# Pendulum_Lamp_PCB.net
KiCad netlist of a schematic drawn in EAGLE
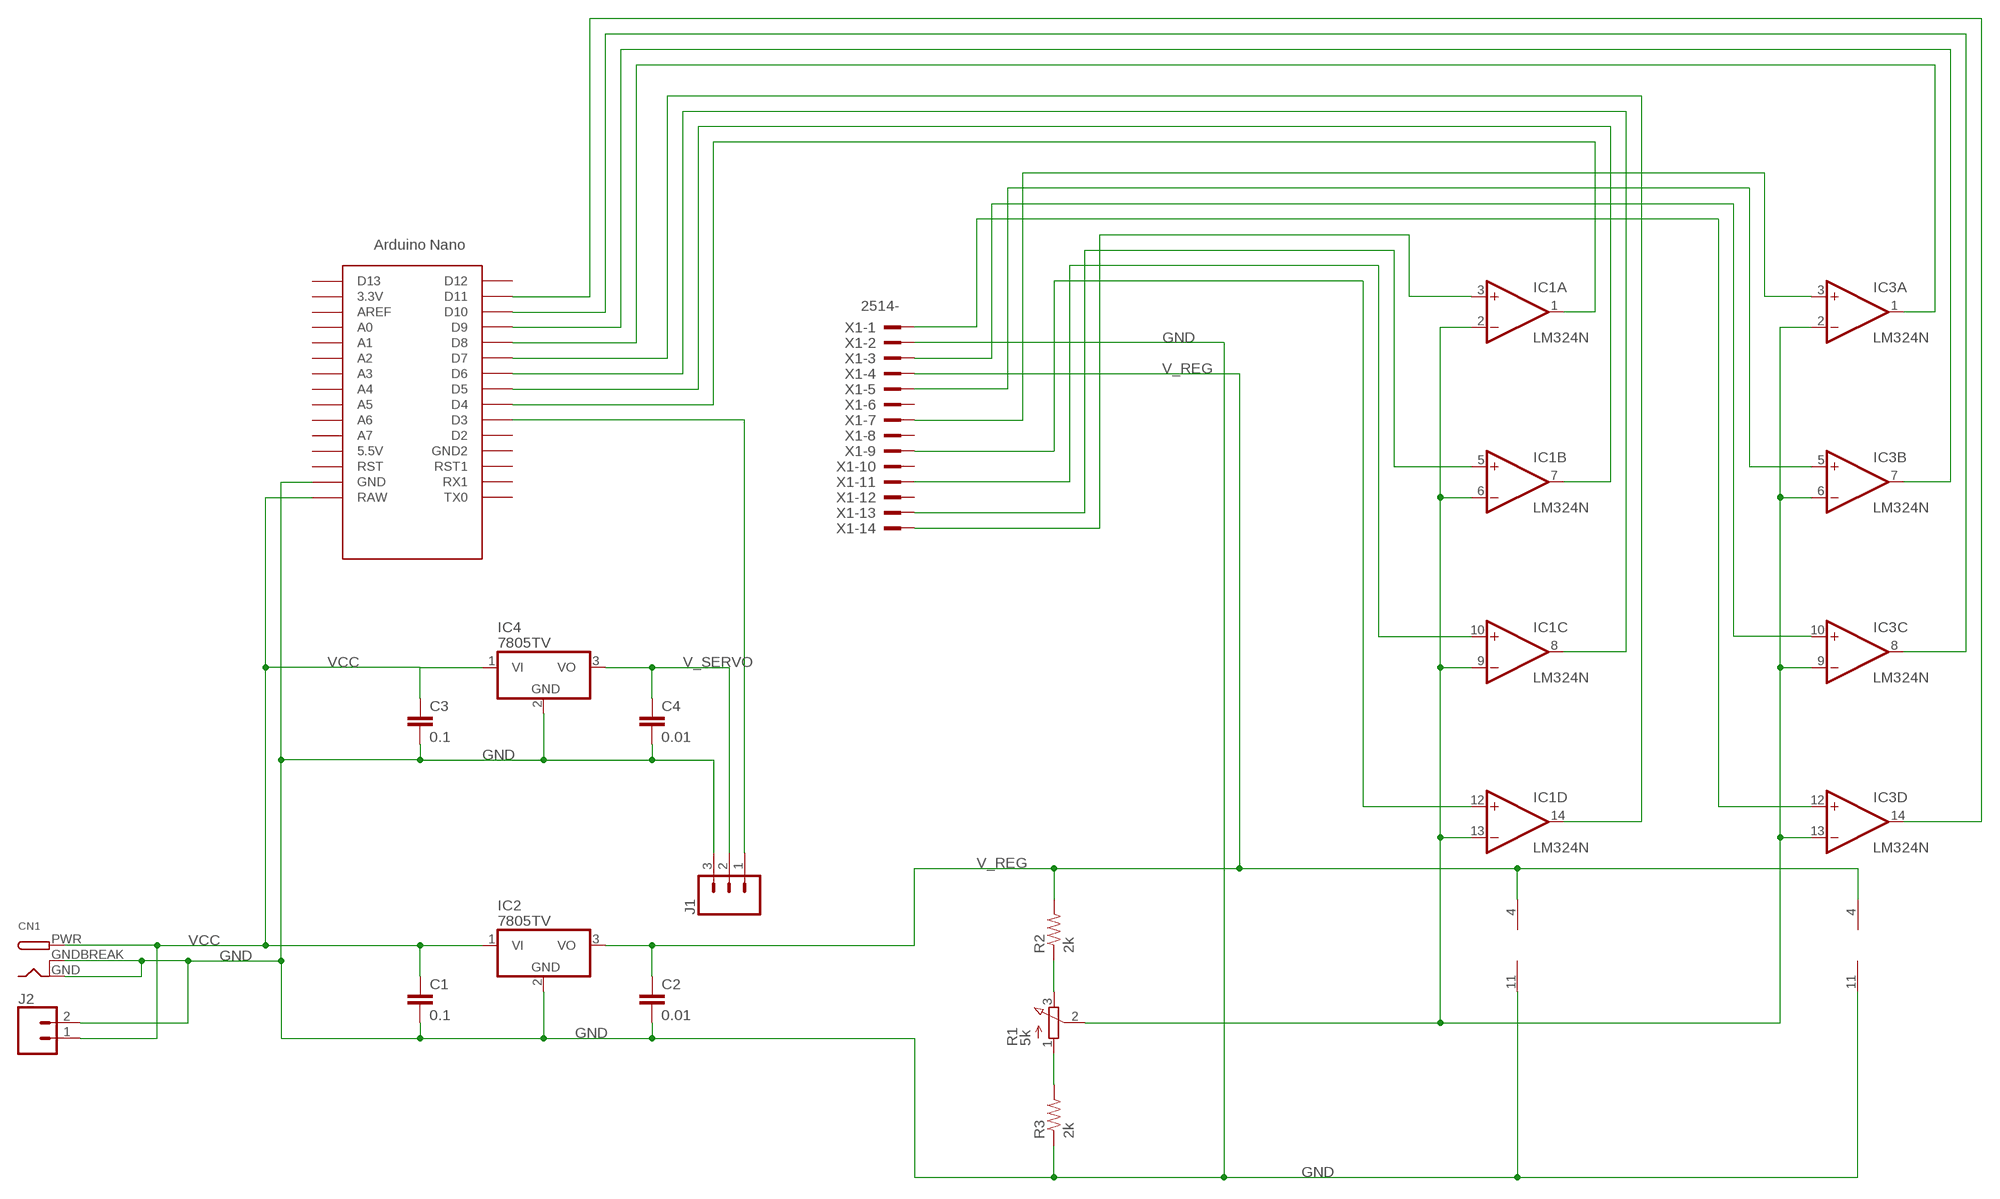
[diagram p0: schematic, sheet 1]

(export (version "E")
  (design (tool "Eeschema 10.0.6"))
  (components
    (comp (ref "C1")
      (value "0.1")
      (footprint "eagle-import:C025-030X050")
      (libsource (lib "eagle-import") (part "C-EU025-030X050"))
    )
    (comp (ref "C2")
      (value "0.01")
      (footprint "eagle-import:C025-030X050")
      (libsource (lib "eagle-import") (part "C-EU025-030X050"))
    )
    (comp (ref "C3")
      (value "0.1")
      (footprint "eagle-import:C025-030X050")
      (libsource (lib "eagle-import") (part "C-EU025-030X050"))
    )
    (comp (ref "C4")
      (value "0.01")
      (footprint "eagle-import:C025-030X050")
      (libsource (lib "eagle-import") (part "C-EU025-030X050"))
    )
    (comp (ref "CN1")
      (value "DCBARRELPTH")
      (footprint "eagle-import:DCJACK_2MM_PTH")
      (libsource (lib "eagle-import") (part "DCBARRELPTH"))
    )
    (comp (ref "IC1")
      (value "LM324N")
      (footprint "eagle-import:DIL14")
      (libsource (lib "eagle-import") (part "LM324N"))
    )
    (comp (ref "IC2")
      (value "7805TV")
      (footprint "eagle-import:TO220V")
      (libsource (lib "eagle-import") (part "78TV05"))
    )
    (comp (ref "IC3")
      (value "LM324N")
      (footprint "eagle-import:DIL14")
      (libsource (lib "eagle-import") (part "LM324N"))
    )
    (comp (ref "IC4")
      (value "7805TV")
      (footprint "eagle-import:TO220V")
      (libsource (lib "eagle-import") (part "78TV05"))
    )
    (comp (ref "J1")
      (value "CONN_03LONGPADS")
      (footprint "eagle-import:1X03_LONGPADS")
      (libsource (lib "eagle-import") (part "CONN_03LONGPADS"))
    )
    (comp (ref "J2")
      (value "CONN_023.5MM_LOCK")
      (footprint "eagle-import:SCREWTERMINAL-3.5MM-2_LOCK")
      (libsource (lib "eagle-import") (part "CONN_023.5MM_LOCK"))
    )
    (comp (ref "R1")
      (value "5k")
      (footprint "eagle-import:3RP_1610N")
      (libsource (lib "eagle-import") (part "3RP/1610N"))
    )
    (comp (ref "R2")
      (value "2k")
      (footprint "eagle-import:0204_7")
      (libsource (lib "eagle-import") (part "R-US_0204/7"))
    )
    (comp (ref "R3")
      (value "2k")
      (footprint "eagle-import:0204_7")
      (libsource (lib "eagle-import") (part "R-US_0204/7"))
    )
    (comp (ref "U$1")
      (value "NANO")
      (footprint "eagle-import:NANO")
      (libsource (lib "eagle-import") (part "NANO"))
    )
    (comp (ref "X1")
      (value "2514-")
      (footprint "eagle-import:PAK100_2500-14")
      (libsource (lib "eagle-import") (part "2514-"))
    )
  )
  (nets
    (net (code "1") (name "/GND") (class "Default")
      (node (ref "C1") (pin "2") (pinfunction "2_2") (pintype "passive"))
      (node (ref "C2") (pin "2") (pinfunction "2_2") (pintype "passive"))
      (node (ref "C3") (pin "2") (pinfunction "2_2") (pintype "passive"))
      (node (ref "C4") (pin "2") (pinfunction "2_2") (pintype "passive"))
      (node (ref "CN1") (pin "GND") (pinfunction "GND_GND") (pintype "power_in"))
      (node (ref "CN1") (pin "GNDBREAK") (pinfunction "GNDBREAK_GNDBREAK") (pintype "power_in"))
      (node (ref "IC1") (pin "11") (pinfunction "V-_11") (pintype "power_in"))
      (node (ref "IC2") (pin "2") (pinfunction "GND_2") (pintype "passive"))
      (node (ref "IC3") (pin "11") (pinfunction "V-_11") (pintype "power_in"))
      (node (ref "IC4") (pin "2") (pinfunction "GND_2") (pintype "passive"))
      (node (ref "J1") (pin "3") (pinfunction "3_3") (pintype "passive"))
      (node (ref "J2") (pin "2") (pinfunction "2_2") (pintype "passive"))
      (node (ref "R3") (pin "1") (pinfunction "1_1") (pintype "passive"))
      (node (ref "U$1") (pin "GND") (pinfunction "GND_GND") (pintype "bidirectional"))
      (node (ref "X1") (pin "2") (pinfunction "KL_2") (pintype "passive"))
    )
    (net (code "2") (name "/VCC") (class "Default")
      (node (ref "C1") (pin "1") (pinfunction "1_1") (pintype "passive"))
      (node (ref "C3") (pin "1") (pinfunction "1_1") (pintype "passive"))
      (node (ref "CN1") (pin "PWR") (pinfunction "PWR_PWR") (pintype "power_in"))
      (node (ref "IC2") (pin "1") (pinfunction "VI_1") (pintype "input"))
      (node (ref "IC4") (pin "1") (pinfunction "VI_1") (pintype "input"))
      (node (ref "J2") (pin "1") (pinfunction "1_1") (pintype "passive"))
      (node (ref "U$1") (pin "RAW") (pinfunction "RAW_RAW") (pintype "bidirectional"))
    )
    (net (code "3") (name "/V_REG") (class "Default")
      (node (ref "C2") (pin "1") (pinfunction "1_1") (pintype "passive"))
      (node (ref "IC1") (pin "4") (pinfunction "V+_4") (pintype "power_in"))
      (node (ref "IC2") (pin "3") (pinfunction "VO_3") (pintype "passive"))
      (node (ref "IC3") (pin "4") (pinfunction "V+_4") (pintype "power_in"))
      (node (ref "R2") (pin "2") (pinfunction "2_2") (pintype "passive"))
      (node (ref "X1") (pin "4") (pinfunction "KL_4") (pintype "passive"))
    )
    (net (code "4") (name "/V_SERVO") (class "Default")
      (node (ref "C4") (pin "1") (pinfunction "1_1") (pintype "passive"))
      (node (ref "IC4") (pin "3") (pinfunction "VO_3") (pintype "passive"))
      (node (ref "J1") (pin "2") (pinfunction "2_2") (pintype "passive"))
    )
    (net (code "5") (name "Net-(IC1A-+IN)") (class "Default")
      (node (ref "IC1") (pin "3") (pinfunction "+IN_3") (pintype "input"))
      (node (ref "X1") (pin "14") (pinfunction "KL_14") (pintype "passive"))
    )
    (net (code "6") (name "Net-(IC1A--IN)") (class "Default")
      (node (ref "IC1") (pin "13") (pinfunction "-IN_13") (pintype "input"))
      (node (ref "IC1") (pin "2") (pinfunction "-IN_2") (pintype "input"))
      (node (ref "IC1") (pin "6") (pinfunction "-IN_6") (pintype "input"))
      (node (ref "IC1") (pin "9") (pinfunction "-IN_9") (pintype "input"))
      (node (ref "IC3") (pin "13") (pinfunction "-IN_13") (pintype "input"))
      (node (ref "IC3") (pin "2") (pinfunction "-IN_2") (pintype "input"))
      (node (ref "IC3") (pin "6") (pinfunction "-IN_6") (pintype "input"))
      (node (ref "IC3") (pin "9") (pinfunction "-IN_9") (pintype "input"))
      (node (ref "R1") (pin "2") (pinfunction "S_2") (pintype "passive"))
    )
    (net (code "7") (name "Net-(IC1A-OUT)") (class "Default")
      (node (ref "IC1") (pin "1") (pinfunction "OUT_1") (pintype "output"))
      (node (ref "U$1") (pin "D4") (pinfunction "D4_D4") (pintype "bidirectional"))
    )
    (net (code "8") (name "Net-(IC1B-+IN)") (class "Default")
      (node (ref "IC1") (pin "5") (pinfunction "+IN_5") (pintype "input"))
      (node (ref "X1") (pin "13") (pinfunction "KL_13") (pintype "passive"))
    )
    (net (code "9") (name "Net-(IC1B-OUT)") (class "Default")
      (node (ref "IC1") (pin "7") (pinfunction "OUT_7") (pintype "output"))
      (node (ref "U$1") (pin "D5") (pinfunction "D5_D5") (pintype "bidirectional"))
    )
    (net (code "10") (name "Net-(IC1C-+IN)") (class "Default")
      (node (ref "IC1") (pin "10") (pinfunction "+IN_10") (pintype "input"))
      (node (ref "X1") (pin "11") (pinfunction "KL_11") (pintype "passive"))
    )
    (net (code "11") (name "Net-(IC1C-OUT)") (class "Default")
      (node (ref "IC1") (pin "8") (pinfunction "OUT_8") (pintype "output"))
      (node (ref "U$1") (pin "D6") (pinfunction "D6_D6") (pintype "bidirectional"))
    )
    (net (code "12") (name "Net-(IC1D-+IN)") (class "Default")
      (node (ref "IC1") (pin "12") (pinfunction "+IN_12") (pintype "input"))
      (node (ref "X1") (pin "9") (pinfunction "KL_9") (pintype "passive"))
    )
    (net (code "13") (name "Net-(IC1D-OUT)") (class "Default")
      (node (ref "IC1") (pin "14") (pinfunction "OUT_14") (pintype "output"))
      (node (ref "U$1") (pin "D7") (pinfunction "D7_D7") (pintype "bidirectional"))
    )
    (net (code "14") (name "Net-(IC3A-+IN)") (class "Default")
      (node (ref "IC3") (pin "3") (pinfunction "+IN_3") (pintype "input"))
      (node (ref "X1") (pin "7") (pinfunction "KL_7") (pintype "passive"))
    )
    (net (code "15") (name "Net-(IC3A-OUT)") (class "Default")
      (node (ref "IC3") (pin "1") (pinfunction "OUT_1") (pintype "output"))
      (node (ref "U$1") (pin "D8") (pinfunction "D8_D8") (pintype "bidirectional"))
    )
    (net (code "16") (name "Net-(IC3B-+IN)") (class "Default")
      (node (ref "IC3") (pin "5") (pinfunction "+IN_5") (pintype "input"))
      (node (ref "X1") (pin "5") (pinfunction "KL_5") (pintype "passive"))
    )
    (net (code "17") (name "Net-(IC3B-OUT)") (class "Default")
      (node (ref "IC3") (pin "7") (pinfunction "OUT_7") (pintype "output"))
      (node (ref "U$1") (pin "D9") (pinfunction "D9_D9") (pintype "bidirectional"))
    )
    (net (code "18") (name "Net-(IC3C-+IN)") (class "Default")
      (node (ref "IC3") (pin "10") (pinfunction "+IN_10") (pintype "input"))
      (node (ref "X1") (pin "3") (pinfunction "KL_3") (pintype "passive"))
    )
    (net (code "19") (name "Net-(IC3C-OUT)") (class "Default")
      (node (ref "IC3") (pin "8") (pinfunction "OUT_8") (pintype "output"))
      (node (ref "U$1") (pin "D10") (pinfunction "D10_D10") (pintype "bidirectional"))
    )
    (net (code "20") (name "Net-(IC3D-+IN)") (class "Default")
      (node (ref "IC3") (pin "12") (pinfunction "+IN_12") (pintype "input"))
      (node (ref "X1") (pin "1") (pinfunction "KL_1") (pintype "passive"))
    )
    (net (code "21") (name "Net-(IC3D-OUT)") (class "Default")
      (node (ref "IC3") (pin "14") (pinfunction "OUT_14") (pintype "output"))
      (node (ref "U$1") (pin "D11") (pinfunction "D11_D11") (pintype "bidirectional"))
    )
    (net (code "22") (name "Net-(J1-Pad1)") (class "Default")
      (node (ref "J1") (pin "1") (pinfunction "1_1") (pintype "passive"))
      (node (ref "U$1") (pin "D3") (pinfunction "D3_D3") (pintype "bidirectional"))
    )
    (net (code "23") (name "Net-(R1-A)") (class "Default")
      (node (ref "R1") (pin "1") (pinfunction "A_1") (pintype "passive"))
      (node (ref "R3") (pin "2") (pinfunction "2_2") (pintype "passive"))
    )
    (net (code "24") (name "Net-(R1-E)") (class "Default")
      (node (ref "R1") (pin "3") (pinfunction "E_3") (pintype "passive"))
      (node (ref "R2") (pin "1") (pinfunction "1_1") (pintype "passive"))
    )
    (net (code "25") (name "unconnected-(U$1-5.5V-Pad5V)") (class "Default")
      (node (ref "U$1") (pin "5V") (pinfunction "5.5V_5V") (pintype "bidirectional"))
    )
    (net (code "26") (name "unconnected-(U$1-GND2-PadGND1)") (class "Default")
      (node (ref "U$1") (pin "GND1") (pinfunction "GND2_GND1") (pintype "bidirectional"))
    )
    (net (code "27") (name "unconnected-(U$1-Pad3.3V)") (class "Default")
      (node (ref "U$1") (pin "3.3V") (pinfunction "3.3V_3.3V") (pintype "bidirectional"))
    )
    (net (code "28") (name "unconnected-(U$1-PadA0)") (class "Default")
      (node (ref "U$1") (pin "A0") (pinfunction "A0_A0") (pintype "bidirectional"))
    )
    (net (code "29") (name "unconnected-(U$1-PadA1)") (class "Default")
      (node (ref "U$1") (pin "A1") (pinfunction "A1_A1") (pintype "bidirectional"))
    )
    (net (code "30") (name "unconnected-(U$1-PadA2)") (class "Default")
      (node (ref "U$1") (pin "A2") (pinfunction "A2_A2") (pintype "bidirectional"))
    )
    (net (code "31") (name "unconnected-(U$1-PadA3)") (class "Default")
      (node (ref "U$1") (pin "A3") (pinfunction "A3_A3") (pintype "bidirectional"))
    )
    (net (code "32") (name "unconnected-(U$1-PadA4)") (class "Default")
      (node (ref "U$1") (pin "A4") (pinfunction "A4_A4") (pintype "bidirectional"))
    )
    (net (code "33") (name "unconnected-(U$1-PadA5)") (class "Default")
      (node (ref "U$1") (pin "A5") (pinfunction "A5_A5") (pintype "bidirectional"))
    )
    (net (code "34") (name "unconnected-(U$1-PadA6)") (class "Default")
      (node (ref "U$1") (pin "A6") (pinfunction "A6_A6") (pintype "bidirectional"))
    )
    (net (code "35") (name "unconnected-(U$1-PadA7)") (class "Default")
      (node (ref "U$1") (pin "A7") (pinfunction "A7_A7") (pintype "bidirectional"))
    )
    (net (code "36") (name "unconnected-(U$1-PadAREF)") (class "Default")
      (node (ref "U$1") (pin "AREF") (pinfunction "AREF_AREF") (pintype "bidirectional"))
    )
    (net (code "37") (name "unconnected-(U$1-PadD2)") (class "Default")
      (node (ref "U$1") (pin "D2") (pinfunction "D2_D2") (pintype "bidirectional"))
    )
    (net (code "38") (name "unconnected-(U$1-PadD12)") (class "Default")
      (node (ref "U$1") (pin "D12") (pinfunction "D12_D12") (pintype "bidirectional"))
    )
    (net (code "39") (name "unconnected-(U$1-PadD13)") (class "Default")
      (node (ref "U$1") (pin "D13") (pinfunction "D13_D13") (pintype "bidirectional"))
    )
    (net (code "40") (name "unconnected-(U$1-PadICSP1)") (class "Default")
      (node (ref "U$1") (pin "ICSP1") (pinfunction "ICSP1_ICSP1") (pintype "bidirectional"))
    )
    (net (code "41") (name "unconnected-(U$1-PadICSP2)") (class "Default")
      (node (ref "U$1") (pin "ICSP2") (pinfunction "ICSP2_ICSP2") (pintype "bidirectional"))
    )
    (net (code "42") (name "unconnected-(U$1-PadICSP3)") (class "Default")
      (node (ref "U$1") (pin "ICSP3") (pinfunction "ICSP3_ICSP3") (pintype "bidirectional"))
    )
    (net (code "43") (name "unconnected-(U$1-PadICSP4)") (class "Default")
      (node (ref "U$1") (pin "ICSP4") (pinfunction "ICSP4_ICSP4") (pintype "bidirectional"))
    )
    (net (code "44") (name "unconnected-(U$1-PadICSP5)") (class "Default")
      (node (ref "U$1") (pin "ICSP5") (pinfunction "ICSP5_ICSP5") (pintype "bidirectional"))
    )
    (net (code "45") (name "unconnected-(U$1-PadICSP6)") (class "Default")
      (node (ref "U$1") (pin "ICSP6") (pinfunction "ICSP6_ICSP6") (pintype "bidirectional"))
    )
    (net (code "46") (name "unconnected-(U$1-PadRST)") (class "Default")
      (node (ref "U$1") (pin "RST") (pinfunction "RST_RST") (pintype "bidirectional"))
    )
    (net (code "47") (name "unconnected-(U$1-PadRST1)") (class "Default")
      (node (ref "U$1") (pin "RST1") (pinfunction "RST1_RST1") (pintype "bidirectional"))
    )
    (net (code "48") (name "unconnected-(U$1-PadRX1)") (class "Default")
      (node (ref "U$1") (pin "RX1") (pinfunction "RX1_RX1") (pintype "bidirectional"))
    )
    (net (code "49") (name "unconnected-(U$1-PadTX0)") (class "Default")
      (node (ref "U$1") (pin "TX0") (pinfunction "TX0_TX0") (pintype "bidirectional"))
    )
    (net (code "50") (name "unconnected-(X1B-KL-Pad10)") (class "Default")
      (node (ref "X1") (pin "10") (pinfunction "KL_10") (pintype "passive"))
    )
    (net (code "51") (name "unconnected-(X1D-KL-Pad12)") (class "Default")
      (node (ref "X1") (pin "12") (pinfunction "KL_12") (pintype "passive"))
    )
    (net (code "52") (name "unconnected-(X1K-KL-Pad6)") (class "Default")
      (node (ref "X1") (pin "6") (pinfunction "KL_6") (pintype "passive"))
    )
    (net (code "53") (name "unconnected-(X1M-KL-Pad8)") (class "Default")
      (node (ref "X1") (pin "8") (pinfunction "KL_8") (pintype "passive"))
    )
  )
)
